# ENCODER.net
KiCad netlist of a schematic drawn in Altium Designer
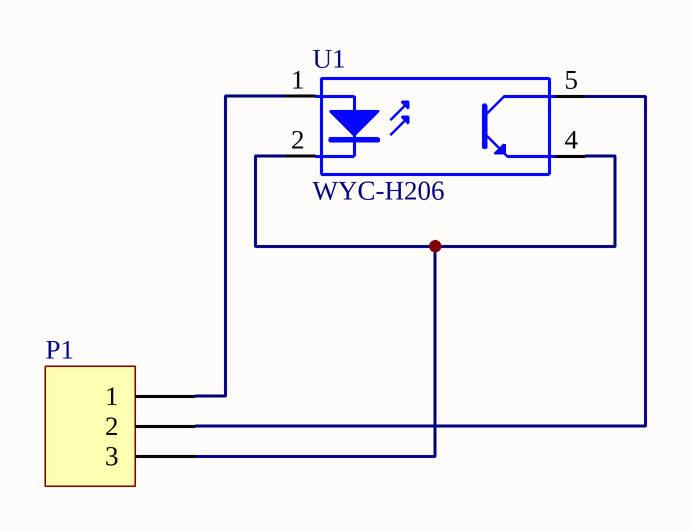
[diagram p0: ENCODER.SchDoc]

(export (version "E")
  (design (tool "Eeschema 10.0.6"))
  (components
    (comp (ref "P1")
      (value "Header 3")
      (footprint "CONN-3POS-PITCH2.54MM")
      (description "Header, 3-Pin")
      (libsource (lib "Miscellaneous Connectors") (part "Header 3"))
    )
    (comp (ref "U1")
      (value "WYC-H206")
      (footprint "ENCODER-WYC-H206")
      (description "4-Pin Phototransistor Optocoupler")
      (libsource (lib "Miscellaneous Devices") (part "Optoisolator1"))
    )
  )
  (nets
    (net (code "1") (name "Net-(U1-A)") (class "Default")
      (node (ref "P1") (pin "1") (pinfunction "1_1") (pintype "passive"))
      (node (ref "U1") (pin "1") (pinfunction "A_1") (pintype "passive"))
    )
    (net (code "2") (name "Net-(U1-C)") (class "Default")
      (node (ref "P1") (pin "2") (pinfunction "2_2") (pintype "passive"))
      (node (ref "U1") (pin "5") (pinfunction "C_5") (pintype "passive"))
    )
    (net (code "3") (name "Net-(U1-E)") (class "Default")
      (node (ref "P1") (pin "3") (pinfunction "3_3") (pintype "passive"))
      (node (ref "U1") (pin "2") (pinfunction "K_2") (pintype "passive"))
      (node (ref "U1") (pin "4") (pinfunction "E_4") (pintype "passive"))
    )
  )
)
